# Line_follower.net
KiCad netlist of a schematic drawn in EAGLE
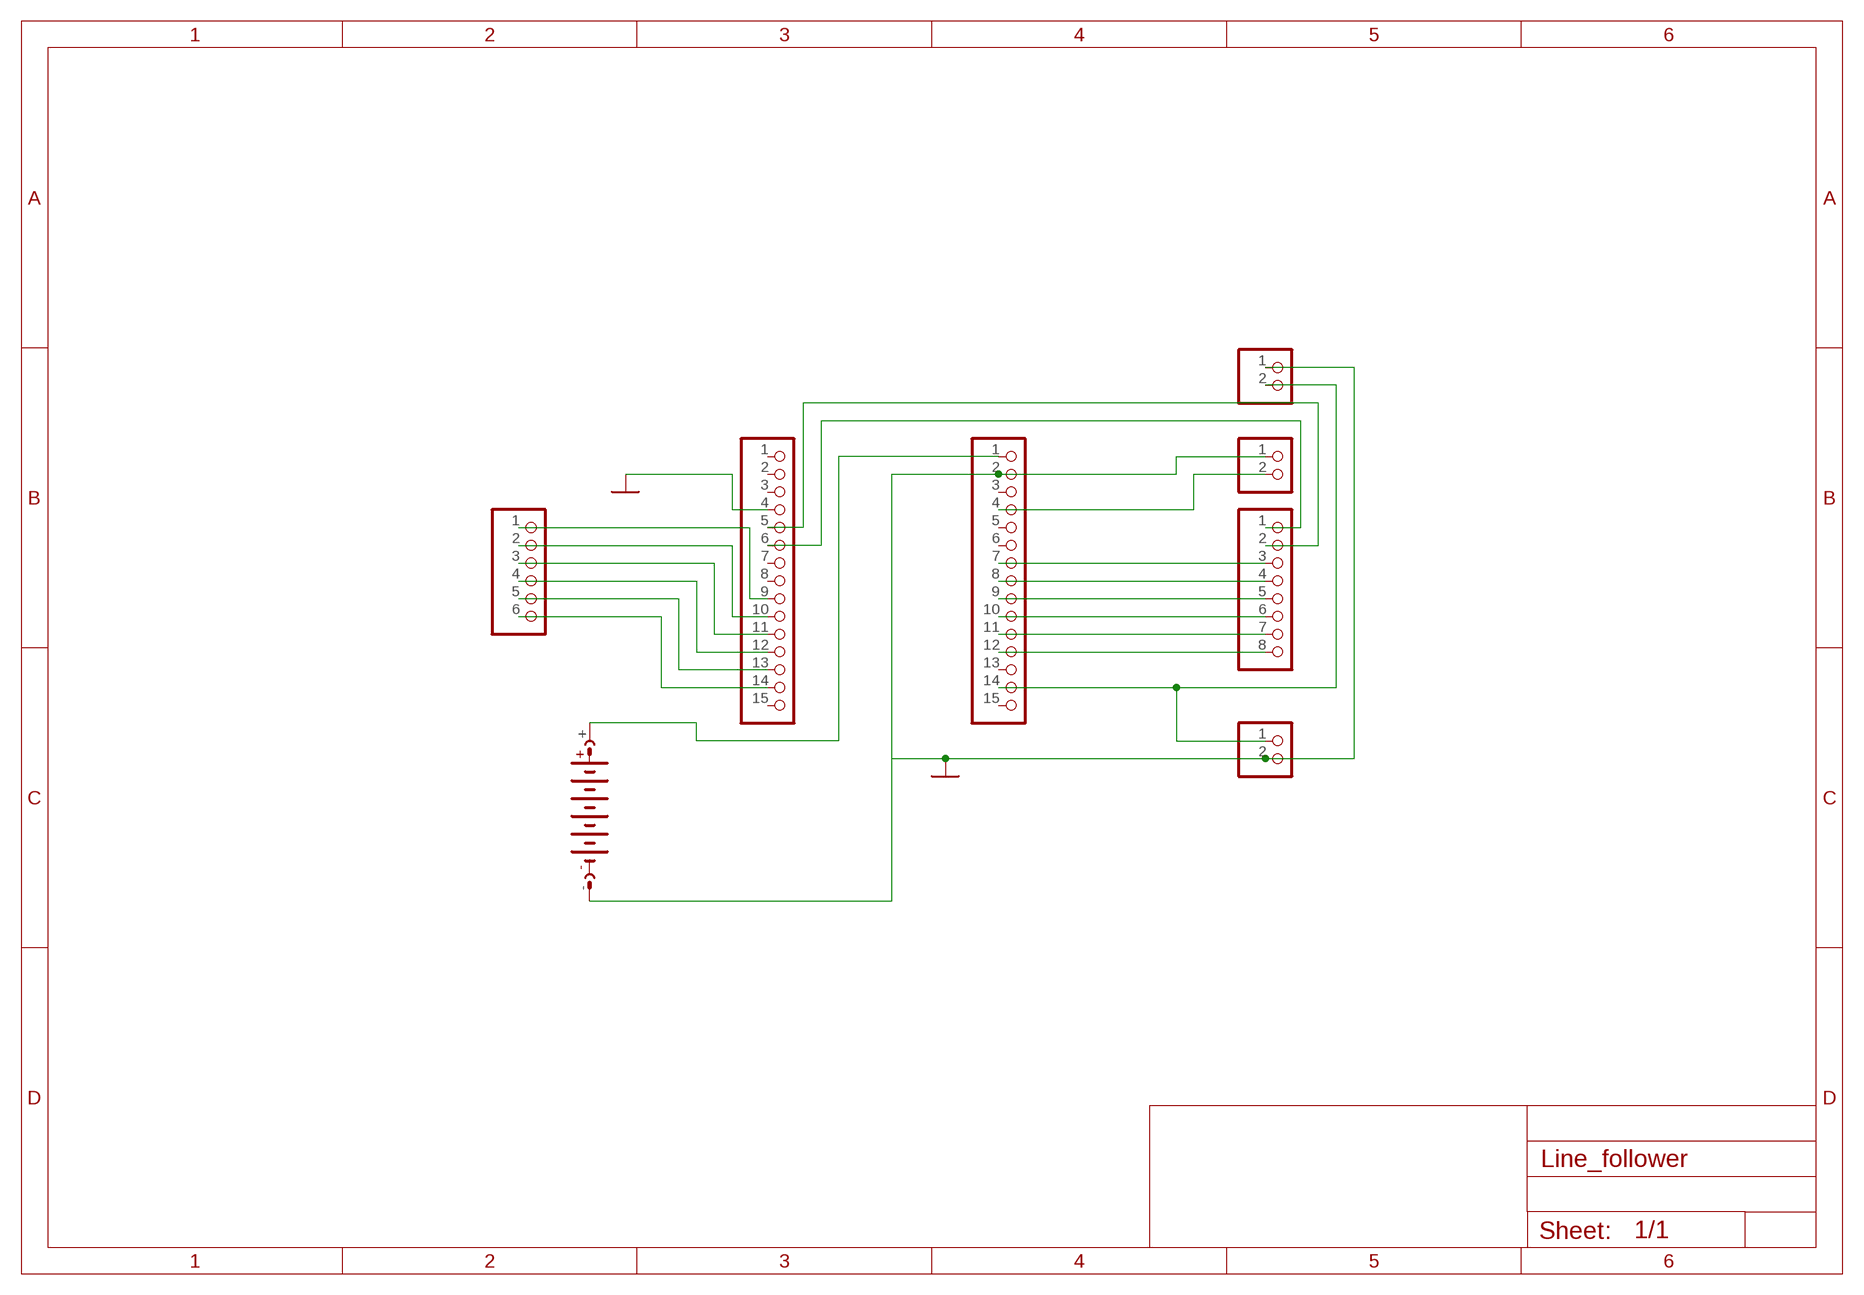
[diagram p0: schematic, sheet 1]

(export (version "E")
  (design (tool "Eeschema 10.0.6"))
  (components
    (comp (ref "G1")
      (value "AB9V")
      (footprint "eagle-import:AB9V")
      (libsource (lib "eagle-import") (part "AB9V"))
    )
    (comp (ref "JP1")
      (value "PINHD-1X15")
      (footprint "eagle-import:1X15")
      (libsource (lib "eagle-import") (part "PINHD-1X15"))
    )
    (comp (ref "JP2")
      (value "PINHD-1X15")
      (footprint "eagle-import:1X15")
      (libsource (lib "eagle-import") (part "PINHD-1X15"))
    )
    (comp (ref "JP3")
      (value "PINHD-1X8")
      (footprint "eagle-import:1X08")
      (libsource (lib "eagle-import") (part "PINHD-1X8"))
    )
    (comp (ref "JP4")
      (value "PINHD-1X6")
      (footprint "eagle-import:1X06")
      (libsource (lib "eagle-import") (part "PINHD-1X6"))
    )
    (comp (ref "JP5")
      (value "PINHD-1X2")
      (footprint "eagle-import:1X02")
      (libsource (lib "eagle-import") (part "PINHD-1X2"))
    )
    (comp (ref "JP6")
      (value "PINHD-1X2")
      (footprint "eagle-import:1X02")
      (libsource (lib "eagle-import") (part "PINHD-1X2"))
    )
    (comp (ref "JP7")
      (value "PINHD-1X2")
      (footprint "eagle-import:1X02")
      (libsource (lib "eagle-import") (part "PINHD-1X2"))
    )
  )
  (nets
    (net (code "1") (name "GND") (class "Default")
      (node (ref "G1") (pin "-") (pinfunction "-_-") (pintype "passive"))
      (node (ref "JP1") (pin "4") (pinfunction "4_4") (pintype "passive"))
      (node (ref "JP2") (pin "2") (pinfunction "2_2") (pintype "passive"))
      (node (ref "JP5") (pin "1") (pinfunction "1_1") (pintype "passive"))
      (node (ref "JP6") (pin "2") (pinfunction "2_2") (pintype "passive"))
      (node (ref "JP7") (pin "1") (pinfunction "1_1") (pintype "passive"))
    )
    (net (code "2") (name "Net-(G1-Pad+)") (class "Default")
      (node (ref "G1") (pin "+") (pinfunction "+_+") (pintype "passive"))
      (node (ref "JP2") (pin "1") (pinfunction "1_1") (pintype "passive"))
    )
    (net (code "3") (name "Net-(JP1-Pad5)") (class "Default")
      (node (ref "JP1") (pin "5") (pinfunction "5_5") (pintype "passive"))
      (node (ref "JP3") (pin "2") (pinfunction "2_2") (pintype "passive"))
    )
    (net (code "4") (name "Net-(JP1-Pad6)") (class "Default")
      (node (ref "JP1") (pin "6") (pinfunction "6_6") (pintype "passive"))
      (node (ref "JP3") (pin "1") (pinfunction "1_1") (pintype "passive"))
    )
    (net (code "5") (name "Net-(JP1-Pad9)") (class "Default")
      (node (ref "JP1") (pin "9") (pinfunction "9_9") (pintype "passive"))
      (node (ref "JP4") (pin "1") (pinfunction "1_1") (pintype "passive"))
    )
    (net (code "6") (name "Net-(JP1-Pad10)") (class "Default")
      (node (ref "JP1") (pin "10") (pinfunction "10_10") (pintype "passive"))
      (node (ref "JP4") (pin "2") (pinfunction "2_2") (pintype "passive"))
    )
    (net (code "7") (name "Net-(JP1-Pad11)") (class "Default")
      (node (ref "JP1") (pin "11") (pinfunction "11_11") (pintype "passive"))
      (node (ref "JP4") (pin "3") (pinfunction "3_3") (pintype "passive"))
    )
    (net (code "8") (name "Net-(JP1-Pad12)") (class "Default")
      (node (ref "JP1") (pin "12") (pinfunction "12_12") (pintype "passive"))
      (node (ref "JP4") (pin "4") (pinfunction "4_4") (pintype "passive"))
    )
    (net (code "9") (name "Net-(JP1-Pad13)") (class "Default")
      (node (ref "JP1") (pin "13") (pinfunction "13_13") (pintype "passive"))
      (node (ref "JP4") (pin "5") (pinfunction "5_5") (pintype "passive"))
    )
    (net (code "10") (name "Net-(JP1-Pad14)") (class "Default")
      (node (ref "JP1") (pin "14") (pinfunction "14_14") (pintype "passive"))
      (node (ref "JP4") (pin "6") (pinfunction "6_6") (pintype "passive"))
    )
    (net (code "11") (name "Net-(JP2-Pad4)") (class "Default")
      (node (ref "JP2") (pin "4") (pinfunction "4_4") (pintype "passive"))
      (node (ref "JP7") (pin "2") (pinfunction "2_2") (pintype "passive"))
    )
    (net (code "12") (name "Net-(JP2-Pad7)") (class "Default")
      (node (ref "JP2") (pin "7") (pinfunction "7_7") (pintype "passive"))
      (node (ref "JP3") (pin "3") (pinfunction "3_3") (pintype "passive"))
    )
    (net (code "13") (name "Net-(JP2-Pad8)") (class "Default")
      (node (ref "JP2") (pin "8") (pinfunction "8_8") (pintype "passive"))
      (node (ref "JP3") (pin "4") (pinfunction "4_4") (pintype "passive"))
    )
    (net (code "14") (name "Net-(JP2-Pad9)") (class "Default")
      (node (ref "JP2") (pin "9") (pinfunction "9_9") (pintype "passive"))
      (node (ref "JP3") (pin "5") (pinfunction "5_5") (pintype "passive"))
    )
    (net (code "15") (name "Net-(JP2-Pad10)") (class "Default")
      (node (ref "JP2") (pin "10") (pinfunction "10_10") (pintype "passive"))
      (node (ref "JP3") (pin "6") (pinfunction "6_6") (pintype "passive"))
    )
    (net (code "16") (name "Net-(JP2-Pad11)") (class "Default")
      (node (ref "JP2") (pin "11") (pinfunction "11_11") (pintype "passive"))
      (node (ref "JP3") (pin "7") (pinfunction "7_7") (pintype "passive"))
    )
    (net (code "17") (name "Net-(JP2-Pad12)") (class "Default")
      (node (ref "JP2") (pin "12") (pinfunction "12_12") (pintype "passive"))
      (node (ref "JP3") (pin "8") (pinfunction "8_8") (pintype "passive"))
    )
    (net (code "18") (name "Net-(JP2-Pad14)") (class "Default")
      (node (ref "JP2") (pin "14") (pinfunction "14_14") (pintype "passive"))
      (node (ref "JP5") (pin "2") (pinfunction "2_2") (pintype "passive"))
      (node (ref "JP6") (pin "1") (pinfunction "1_1") (pintype "passive"))
    )
    (net (code "19") (name "unconnected-(JP1-Pad1)") (class "Default")
      (node (ref "JP1") (pin "1") (pinfunction "1_1") (pintype "passive"))
    )
    (net (code "20") (name "unconnected-(JP1-Pad2)") (class "Default")
      (node (ref "JP1") (pin "2") (pinfunction "2_2") (pintype "passive"))
    )
    (net (code "21") (name "unconnected-(JP1-Pad3)") (class "Default")
      (node (ref "JP1") (pin "3") (pinfunction "3_3") (pintype "passive"))
    )
    (net (code "22") (name "unconnected-(JP1-Pad7)") (class "Default")
      (node (ref "JP1") (pin "7") (pinfunction "7_7") (pintype "passive"))
    )
    (net (code "23") (name "unconnected-(JP1-Pad8)") (class "Default")
      (node (ref "JP1") (pin "8") (pinfunction "8_8") (pintype "passive"))
    )
    (net (code "24") (name "unconnected-(JP1-Pad15)") (class "Default")
      (node (ref "JP1") (pin "15") (pinfunction "15_15") (pintype "passive"))
    )
    (net (code "25") (name "unconnected-(JP2-Pad3)") (class "Default")
      (node (ref "JP2") (pin "3") (pinfunction "3_3") (pintype "passive"))
    )
    (net (code "26") (name "unconnected-(JP2-Pad5)") (class "Default")
      (node (ref "JP2") (pin "5") (pinfunction "5_5") (pintype "passive"))
    )
    (net (code "27") (name "unconnected-(JP2-Pad6)") (class "Default")
      (node (ref "JP2") (pin "6") (pinfunction "6_6") (pintype "passive"))
    )
    (net (code "28") (name "unconnected-(JP2-Pad13)") (class "Default")
      (node (ref "JP2") (pin "13") (pinfunction "13_13") (pintype "passive"))
    )
    (net (code "29") (name "unconnected-(JP2-Pad15)") (class "Default")
      (node (ref "JP2") (pin "15") (pinfunction "15_15") (pintype "passive"))
    )
  )
)
